# Boost.net
KiCad netlist of a schematic drawn in Altium Designer
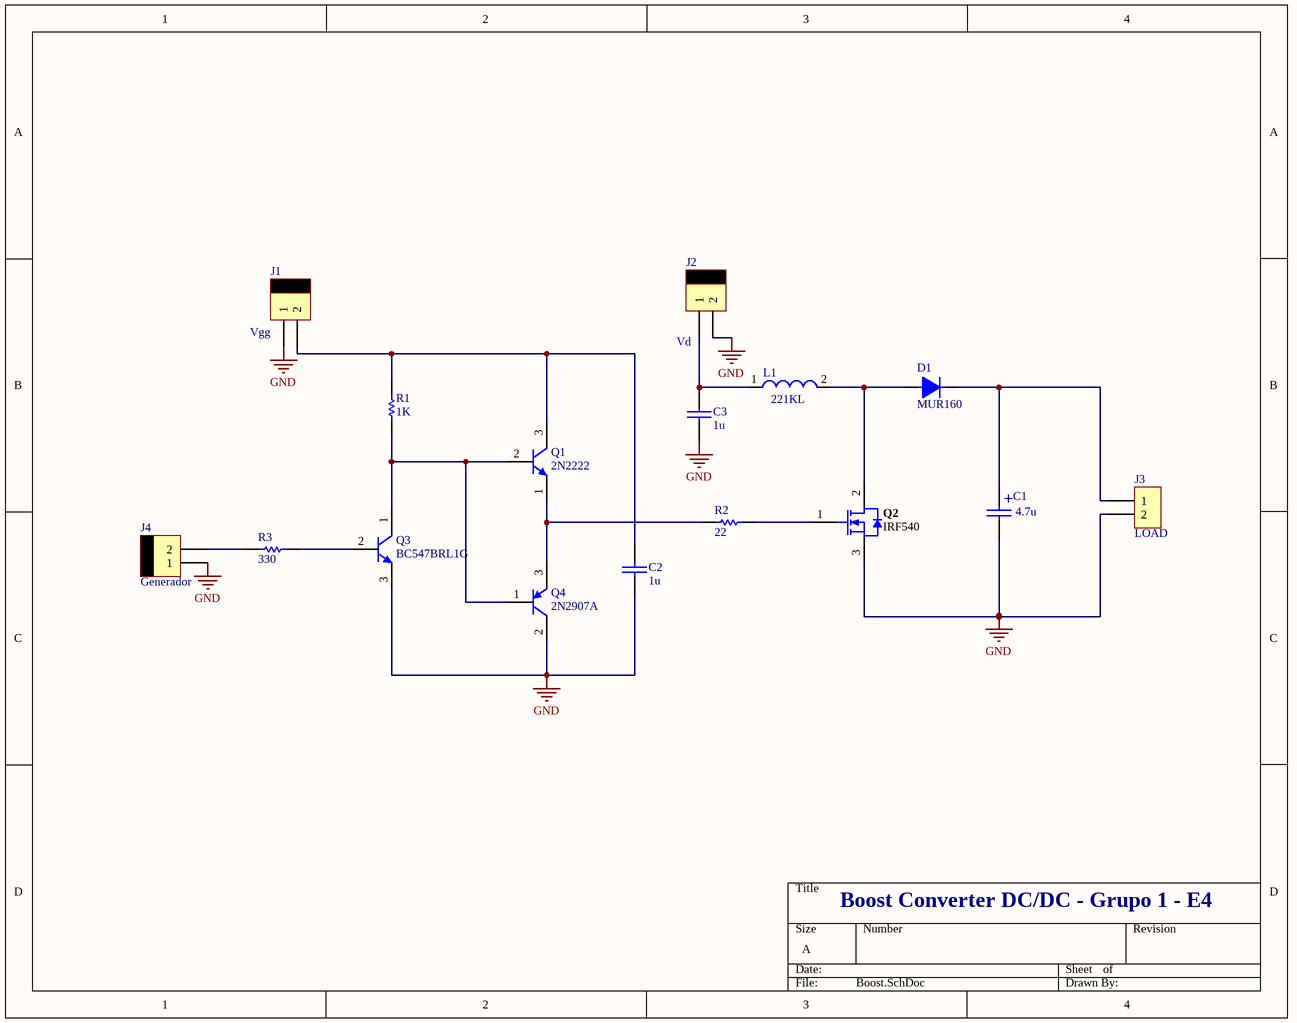
[diagram p0: Boost.SchDoc]

(export (version "E")
  (design (tool "Eeschema 10.0.6"))
  (components
    (comp (ref "C1") (value "4.7u") (footprint "CAP100RP") (libsource (lib "LIBEBAL Tobi") (part "CAPPOL")))
    (comp (ref "C2") (value "1u") (footprint "0805") (libsource (lib "LIBEBAL Tobi") (part "CAP")))
    (comp (ref "C3") (value "1u") (footprint "0805") (libsource (lib "LIBEBAL Tobi") (part "CAP")))
    (comp (ref "D1") (value "MUR160") (footprint "DO41") (libsource (lib "LIBEBAL Tobi") (part "DIODO")))
    (comp (ref "J1") (value "Vgg") (footprint "MOLEX2") (libsource (lib "LIBEBAL Tobi") (part "MOLEX2")))
    (comp (ref "J2") (value "Vd") (footprint "MOLEX2") (libsource (lib "LIBEBAL Tobi") (part "MOLEX2")))
    (comp (ref "J3")
      (value "LOAD")
      (footprint "BORNERA2")
      (libsource (lib "LIBEBAL Tobi") (part "BORNERA 2"))
    )
    (comp (ref "J4") (value "Generador") (footprint "MOLEX2") (libsource (lib "") (part "MOLEX2_1")))
    (comp (ref "L1")
      (value "221KL")
      (footprint "WE-TI-L")
      (description "Radial Leaded Wire Wound Inductor WE-TI, L = 22.0 µH")
      (libsource (lib "Altium Content Vault") (part "PAS-IND-INDUCTOR-2"))
    )
    (comp (ref "Q1")
      (value "2N2222")
      (footprint "MLTC-TO-18-3")
      (description "Low Power Bipolar NPN Transistor, 30 V, -65 to 200 degC, 3-Pin TO-18, RoHS, Bulk")
      (fields (field (name "MANUFACTURER") "Multicomp"))
      (libsource (lib "Altium Content Vault") (part "BJT-NPN-EBC-3"))
    )
    (comp (ref "Q2")
      (value "IRF540")
      (footprint "VISH-TO-220AB-3_A")
      (description "Power MOSFET, 100 VDS, -55 to 175 degC, 3-Pin TO-220AB, RoHS, Tube")
      (fields (field (name "MANUFACTURER") "Vishay"))
      (libsource (lib "Altium Content Vault") (part "NEMOS-GDS-3"))
    )
    (comp (ref "Q3")
      (value "BC547BRL1G")
      (footprint "ONSC-TO-92-3-29-11_AM_BL")
      (description "Amplifier Transistor, NPN Silicon, 3-Pin TO-92, Pb-Free, Tape and Reel")
      (fields (field (name "MANUFACTURER") "On Semiconductor"))
      (libsource (lib "Altium Content Vault") (part "ONSC-NPN-C1B2E3-3"))
    )
    (comp (ref "Q4")
      (value "2N2907A")
      (footprint "STM-TO-18-3")
      (description "Small Signal PNP Transistor, 0.4 W, 60 V, 600 mA, 3-Pin TO-18, RoHS, Bulk")
      (fields (field (name "MANUFACTURER") "STMicroelectronics"))
      (libsource (lib "Altium Content Vault") (part "BJT-PNP-BCE-3"))
    )
    (comp (ref "R1") (value "1K") (footprint "0805") (libsource (lib "LIBEBAL Tobi") (part "RES")))
    (comp (ref "R2") (value "22") (footprint "RES400") (libsource (lib "LIBEBAL Tobi") (part "RES")))
    (comp (ref "R3") (value "330") (footprint "0805") (libsource (lib "LIBEBAL Tobi") (part "RES")))
  )
  (nets
    (net (code "1") (name "GND") (class "Default")
      (node (ref "C1") (pin "2") (pinfunction "2_2") (pintype "passive"))
      (node (ref "C2") (pin "1") (pinfunction "1_1") (pintype "passive"))
      (node (ref "C3") (pin "1") (pinfunction "1_1") (pintype "passive"))
      (node (ref "J1") (pin "1") (pinfunction "1_1") (pintype "passive"))
      (node (ref "J2") (pin "2") (pinfunction "2_2") (pintype "passive"))
      (node (ref "J3") (pin "2") (pinfunction "2_2") (pintype "passive"))
      (node (ref "J4") (pin "1") (pinfunction "1_1") (pintype "passive"))
      (node (ref "Q2") (pin "3") (pinfunction "S_3") (pintype "passive"))
      (node (ref "Q3") (pin "3") (pinfunction "E_3") (pintype "passive"))
      (node (ref "Q4") (pin "2") (pinfunction "C_2") (pintype "passive"))
    )
    (net (code "2") (name "Net-(C1-Pad1)") (class "Default")
      (node (ref "C1") (pin "1") (pinfunction "1_1") (pintype "passive"))
      (node (ref "D1") (pin "2") (pinfunction "2_2") (pintype "passive"))
      (node (ref "J3") (pin "1") (pinfunction "1_1") (pintype "passive"))
    )
    (net (code "3") (name "Net-(C3-Pad2)") (class "Default")
      (node (ref "C3") (pin "2") (pinfunction "2_2") (pintype "passive"))
      (node (ref "J2") (pin "1") (pinfunction "1_1") (pintype "passive"))
      (node (ref "L1") (pin "1") (pinfunction "1_1") (pintype "passive"))
    )
    (net (code "4") (name "Net-(J4-Pad2)") (class "Default")
      (node (ref "J4") (pin "2") (pinfunction "2_2") (pintype "passive"))
      (node (ref "R3") (pin "1") (pinfunction "1_1") (pintype "passive"))
    )
    (net (code "5") (name "Net-(Q1-B)") (class "Default")
      (node (ref "Q1") (pin "2") (pinfunction "B_2") (pintype "passive"))
      (node (ref "Q3") (pin "1") (pinfunction "C_1") (pintype "passive"))
      (node (ref "Q4") (pin "1") (pinfunction "B_1") (pintype "passive"))
      (node (ref "R1") (pin "1") (pinfunction "1_1") (pintype "passive"))
    )
    (net (code "6") (name "Net-(Q1-C)") (class "Default")
      (node (ref "C2") (pin "2") (pinfunction "2_2") (pintype "passive"))
      (node (ref "J1") (pin "2") (pinfunction "2_2") (pintype "passive"))
      (node (ref "Q1") (pin "3") (pinfunction "C_3") (pintype "passive"))
      (node (ref "R1") (pin "2") (pinfunction "2_2") (pintype "passive"))
    )
    (net (code "7") (name "Net-(Q1-E)") (class "Default")
      (node (ref "Q1") (pin "1") (pinfunction "E_1") (pintype "passive"))
      (node (ref "Q4") (pin "3") (pinfunction "E_3") (pintype "passive"))
      (node (ref "R2") (pin "1") (pinfunction "1_1") (pintype "passive"))
    )
    (net (code "8") (name "Net-(Q2-D)") (class "Default")
      (node (ref "D1") (pin "1") (pinfunction "1_1") (pintype "passive"))
      (node (ref "L1") (pin "2") (pinfunction "2_2") (pintype "passive"))
      (node (ref "Q2") (pin "2") (pinfunction "D_2") (pintype "passive"))
    )
    (net (code "9") (name "Net-(Q2-G)") (class "Default")
      (node (ref "Q2") (pin "1") (pinfunction "G_1") (pintype "passive"))
      (node (ref "R2") (pin "2") (pinfunction "2_2") (pintype "passive"))
    )
    (net (code "10") (name "Net-(Q3-B)") (class "Default")
      (node (ref "Q3") (pin "2") (pinfunction "B_2") (pintype "passive"))
      (node (ref "R3") (pin "2") (pinfunction "2_2") (pintype "passive"))
    )
  )
)
